# pj13_duplicate.net
KiCad netlist of a schematic drawn in EAGLE
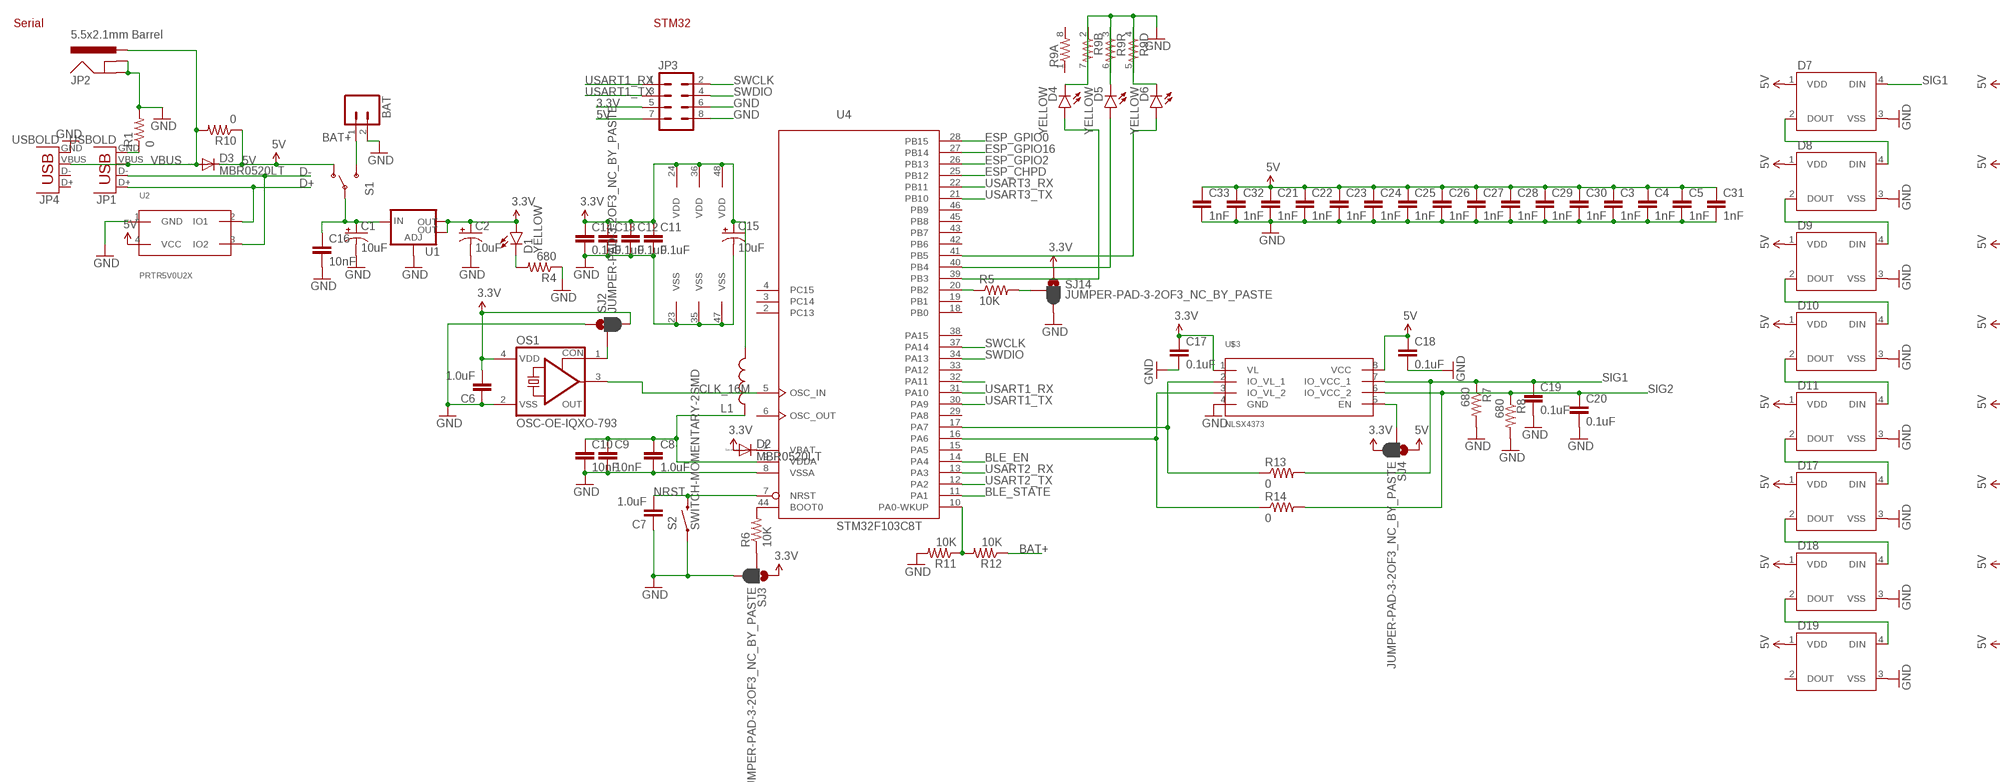
[diagram p0: schematic, sheet 1, part 1 of 2]
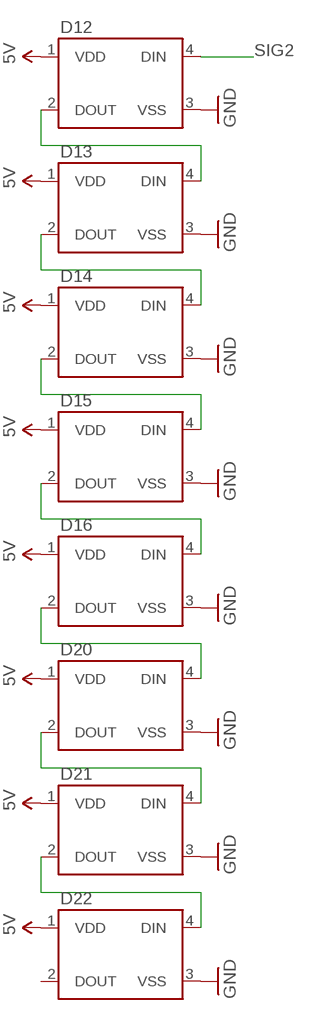
[diagram p1: schematic, sheet 1, part 2 of 2]

(export (version "E")
  (design (tool "Eeschema 10.0.6"))
  (components
    (comp (ref "BAT")
      (value "M02LOCK")
      (footprint "eagle-import:1X02_LOCK")
      (libsource (lib "eagle-import") (part "M02LOCK"))
    )
    (comp (ref "C1")
      (value "10uF")
      (footprint "eagle-import:EIA3216")
      (libsource (lib "eagle-import") (part "10UF-16V-10%(TANT)"))
    )
    (comp (ref "C2")
      (value "10uF")
      (footprint "eagle-import:EIA3216")
      (libsource (lib "eagle-import") (part "10UF-16V-10%(TANT)"))
    )
    (comp (ref "C3")
      (value "1nF")
      (footprint "eagle-import:0603-CAP")
      (libsource (lib "eagle-import") (part "0.1UF-25V-5%(0603)"))
    )
    (comp (ref "C4")
      (value "1nF")
      (footprint "eagle-import:0603-CAP")
      (libsource (lib "eagle-import") (part "0.1UF-25V-5%(0603)"))
    )
    (comp (ref "C5")
      (value "1nF")
      (footprint "eagle-import:0603-CAP")
      (libsource (lib "eagle-import") (part "0.1UF-25V-5%(0603)"))
    )
    (comp (ref "C6")
      (value "1.0uF")
      (footprint "eagle-import:0603-CAP")
      (libsource (lib "eagle-import") (part "1.0UF-16V-10%(0603)"))
    )
    (comp (ref "C7")
      (value "1.0uF")
      (footprint "eagle-import:0603-CAP")
      (libsource (lib "eagle-import") (part "1.0UF-16V-10%(0603)"))
    )
    (comp (ref "C8")
      (value "1.0uF")
      (footprint "eagle-import:0603-CAP")
      (libsource (lib "eagle-import") (part "1.0UF-16V-10%(0603)"))
    )
    (comp (ref "C9")
      (value "10nF")
      (footprint "eagle-import:0603-CAP")
      (libsource (lib "eagle-import") (part "10NF/10000PF-50V-10%(0603)"))
    )
    (comp (ref "C10")
      (value "10nF")
      (footprint "eagle-import:0603-CAP")
      (libsource (lib "eagle-import") (part "10NF/10000PF-50V-10%(0603)"))
    )
    (comp (ref "C11")
      (value "0.1uF")
      (footprint "eagle-import:0603-CAP")
      (libsource (lib "eagle-import") (part "0.1UF-25V-5%(0603)"))
    )
    (comp (ref "C12")
      (value "0.1uF")
      (footprint "eagle-import:0603-CAP")
      (libsource (lib "eagle-import") (part "0.1UF-25V-5%(0603)"))
    )
    (comp (ref "C13")
      (value "0.1uF")
      (footprint "eagle-import:0603-CAP")
      (libsource (lib "eagle-import") (part "0.1UF-25V-5%(0603)"))
    )
    (comp (ref "C14")
      (value "0.1uF")
      (footprint "eagle-import:0603-CAP")
      (libsource (lib "eagle-import") (part "0.1UF-25V-5%(0603)"))
    )
    (comp (ref "C15")
      (value "10uF")
      (footprint "eagle-import:EIA3216")
      (libsource (lib "eagle-import") (part "10UF-16V-10%(TANT)"))
    )
    (comp (ref "C16")
      (value "10nF")
      (footprint "eagle-import:0603-CAP")
      (libsource (lib "eagle-import") (part "10NF/10000PF-50V-10%(0603)"))
    )
    (comp (ref "C17")
      (value "0.1uF")
      (footprint "eagle-import:0603-CAP")
      (libsource (lib "eagle-import") (part "0.1UF-25V-5%(0603)"))
    )
    (comp (ref "C18")
      (value "0.1uF")
      (footprint "eagle-import:0603-CAP")
      (libsource (lib "eagle-import") (part "0.1UF-25V-5%(0603)"))
    )
    (comp (ref "C19")
      (value "0.1uF")
      (footprint "eagle-import:0603-CAP")
      (libsource (lib "eagle-import") (part "0.1UF-25V-5%(0603)"))
    )
    (comp (ref "C20")
      (value "0.1uF")
      (footprint "eagle-import:0603-CAP")
      (libsource (lib "eagle-import") (part "0.1UF-25V-5%(0603)"))
    )
    (comp (ref "C21")
      (value "1nF")
      (footprint "eagle-import:0603-CAP")
      (libsource (lib "eagle-import") (part "0.1UF-25V-5%(0603)"))
    )
    (comp (ref "C22")
      (value "1nF")
      (footprint "eagle-import:0603-CAP")
      (libsource (lib "eagle-import") (part "0.1UF-25V-5%(0603)"))
    )
    (comp (ref "C23")
      (value "1nF")
      (footprint "eagle-import:0603-CAP")
      (libsource (lib "eagle-import") (part "0.1UF-25V-5%(0603)"))
    )
    (comp (ref "C24")
      (value "1nF")
      (footprint "eagle-import:0603-CAP")
      (libsource (lib "eagle-import") (part "0.1UF-25V-5%(0603)"))
    )
    (comp (ref "C25")
      (value "1nF")
      (footprint "eagle-import:0603-CAP")
      (libsource (lib "eagle-import") (part "0.1UF-25V-5%(0603)"))
    )
    (comp (ref "C26")
      (value "1nF")
      (footprint "eagle-import:0603-CAP")
      (libsource (lib "eagle-import") (part "0.1UF-25V-5%(0603)"))
    )
    (comp (ref "C27")
      (value "1nF")
      (footprint "eagle-import:0603-CAP")
      (libsource (lib "eagle-import") (part "0.1UF-25V-5%(0603)"))
    )
    (comp (ref "C28")
      (value "1nF")
      (footprint "eagle-import:0603-CAP")
      (libsource (lib "eagle-import") (part "0.1UF-25V-5%(0603)"))
    )
    (comp (ref "C29")
      (value "1nF")
      (footprint "eagle-import:0603-CAP")
      (libsource (lib "eagle-import") (part "0.1UF-25V-5%(0603)"))
    )
    (comp (ref "C30")
      (value "1nF")
      (footprint "eagle-import:0603-CAP")
      (libsource (lib "eagle-import") (part "0.1UF-25V-5%(0603)"))
    )
    (comp (ref "C31")
      (value "1nF")
      (footprint "eagle-import:0603-CAP")
      (libsource (lib "eagle-import") (part "0.1UF-25V-5%(0603)"))
    )
    (comp (ref "C32")
      (value "1nF")
      (footprint "eagle-import:0603-CAP")
      (libsource (lib "eagle-import") (part "0.1UF-25V-5%(0603)"))
    )
    (comp (ref "C33")
      (value "1nF")
      (footprint "eagle-import:0603-CAP")
      (libsource (lib "eagle-import") (part "0.1UF-25V-5%(0603)"))
    )
    (comp (ref "D1")
      (value "YELLOW")
      (footprint "eagle-import:LED-1206")
      (libsource (lib "eagle-import") (part "LED-YELLOW1206"))
    )
    (comp (ref "D2")
      (value "MBR0520LT")
      (footprint "eagle-import:SOD123")
      (libsource (lib "eagle-import") (part "MBR0520LT"))
    )
    (comp (ref "D3")
      (value "MBR0520LT")
      (footprint "eagle-import:SOD123")
      (libsource (lib "eagle-import") (part "MBR0520LT"))
    )
    (comp (ref "D4")
      (value "YELLOW")
      (footprint "eagle-import:LED-1206")
      (libsource (lib "eagle-import") (part "LED-YELLOW1206"))
    )
    (comp (ref "D5")
      (value "YELLOW")
      (footprint "eagle-import:LED-1206")
      (libsource (lib "eagle-import") (part "LED-YELLOW1206"))
    )
    (comp (ref "D6")
      (value "YELLOW")
      (footprint "eagle-import:LED-1206")
      (libsource (lib "eagle-import") (part "LED-YELLOW1206"))
    )
    (comp (ref "D7")
      (value "WS2812B")
      (footprint "eagle-import:WS2812B")
      (libsource (lib "eagle-import") (part "WS2812B"))
    )
    (comp (ref "D8")
      (value "WS2812B")
      (footprint "eagle-import:WS2812B")
      (libsource (lib "eagle-import") (part "WS2812B"))
    )
    (comp (ref "D9")
      (value "WS2812B")
      (footprint "eagle-import:WS2812B")
      (libsource (lib "eagle-import") (part "WS2812B"))
    )
    (comp (ref "D10")
      (value "WS2812B")
      (footprint "eagle-import:WS2812B")
      (libsource (lib "eagle-import") (part "WS2812B"))
    )
    (comp (ref "D11")
      (value "WS2812B")
      (footprint "eagle-import:WS2812B")
      (libsource (lib "eagle-import") (part "WS2812B"))
    )
    (comp (ref "D12")
      (value "WS2812B")
      (footprint "eagle-import:WS2812B")
      (libsource (lib "eagle-import") (part "WS2812B"))
    )
    (comp (ref "D13")
      (value "WS2812B")
      (footprint "eagle-import:WS2812B")
      (libsource (lib "eagle-import") (part "WS2812B"))
    )
    (comp (ref "D14")
      (value "WS2812B")
      (footprint "eagle-import:WS2812B")
      (libsource (lib "eagle-import") (part "WS2812B"))
    )
    (comp (ref "D15")
      (value "WS2812B")
      (footprint "eagle-import:WS2812B")
      (libsource (lib "eagle-import") (part "WS2812B"))
    )
    (comp (ref "D16")
      (value "WS2812B")
      (footprint "eagle-import:WS2812B")
      (libsource (lib "eagle-import") (part "WS2812B"))
    )
    (comp (ref "D17")
      (value "WS2812B")
      (footprint "eagle-import:WS2812B")
      (libsource (lib "eagle-import") (part "WS2812B"))
    )
    (comp (ref "D18")
      (value "WS2812B")
      (footprint "eagle-import:WS2812B")
      (libsource (lib "eagle-import") (part "WS2812B"))
    )
    (comp (ref "D19")
      (value "WS2812B")
      (footprint "eagle-import:WS2812B")
      (libsource (lib "eagle-import") (part "WS2812B"))
    )
    (comp (ref "D20")
      (value "WS2812B")
      (footprint "eagle-import:WS2812B")
      (libsource (lib "eagle-import") (part "WS2812B"))
    )
    (comp (ref "D21")
      (value "WS2812B")
      (footprint "eagle-import:WS2812B")
      (libsource (lib "eagle-import") (part "WS2812B"))
    )
    (comp (ref "D22")
      (value "WS2812B")
      (footprint "eagle-import:WS2812B")
      (libsource (lib "eagle-import") (part "WS2812B"))
    )
    (comp (ref "JP1")
      (value "USBOLD")
      (footprint "eagle-import:USB-MINIB-OLD")
      (libsource (lib "eagle-import") (part "USBOLD"))
    )
    (comp (ref "JP2")
      (value "5.5x2.1mm Barrel")
      (footprint "eagle-import:POWER_JACK_SMD")
      (libsource (lib "eagle-import") (part "POWER_JACKSMD"))
    )
    (comp (ref "JP3")
      (value "M04X2SMD")
      (footprint "eagle-import:2X4_SMD")
      (libsource (lib "eagle-import") (part "M04X2SMD"))
    )
    (comp (ref "JP4")
      (value "USBOLD")
      (footprint "eagle-import:USB-MINIB-OLD")
      (libsource (lib "eagle-import") (part "USBOLD"))
    )
    (comp (ref "L1")
      (value "INDUCTOR0603")
      (footprint "eagle-import:0603")
      (libsource (lib "eagle-import") (part "INDUCTOR0603"))
    )
    (comp (ref "OS1")
      (value "OSC-OE-IQXO-793")
      (footprint "eagle-import:2.5X2-4-PAD")
      (libsource (lib "eagle-import") (part "OSC-OE-IQXO-793"))
    )
    (comp (ref "R1")
      (value "0")
      (footprint "eagle-import:0603")
      (libsource (lib "eagle-import") (part "0OHM-1/10W-5%(0603)"))
    )
    (comp (ref "R4")
      (value "680")
      (footprint "eagle-import:0603-RES")
      (libsource (lib "eagle-import") (part "680OHM1/10W5%(0603)"))
    )
    (comp (ref "R5")
      (value "10K")
      (footprint "eagle-import:0603-RES")
      (libsource (lib "eagle-import") (part "10KOHM-1/10W-1%(0603)0603"))
    )
    (comp (ref "R6")
      (value "10K")
      (footprint "eagle-import:0603-RES")
      (libsource (lib "eagle-import") (part "10KOHM-1/10W-1%(0603)0603"))
    )
    (comp (ref "R7")
      (value "680")
      (footprint "eagle-import:0603-RES")
      (libsource (lib "eagle-import") (part "680OHM1/10W5%(0603)"))
    )
    (comp (ref "R8")
      (value "680")
      (footprint "eagle-import:0603-RES")
      (libsource (lib "eagle-import") (part "680OHM1/10W5%(0603)"))
    )
    (comp (ref "R9")
      (value "RESISTOR-ARRAY0603-ARV")
      (footprint "eagle-import:0603-ARV")
      (libsource (lib "eagle-import") (part "RESISTOR-ARRAY0603-ARV"))
    )
    (comp (ref "R10")
      (value "0")
      (footprint "eagle-import:0603")
      (libsource (lib "eagle-import") (part "0OHM-1/10W-5%(0603)"))
    )
    (comp (ref "R11")
      (value "10K")
      (footprint "eagle-import:0603-RES")
      (libsource (lib "eagle-import") (part "10KOHM-1/10W-1%(0603)0603"))
    )
    (comp (ref "R12")
      (value "10K")
      (footprint "eagle-import:0603-RES")
      (libsource (lib "eagle-import") (part "10KOHM-1/10W-1%(0603)0603"))
    )
    (comp (ref "R13")
      (value "0")
      (footprint "eagle-import:0603-RES")
      (libsource (lib "eagle-import") (part "680OHM1/10W5%(0603)"))
    )
    (comp (ref "R14")
      (value "0")
      (footprint "eagle-import:0603-RES")
      (libsource (lib "eagle-import") (part "680OHM1/10W5%(0603)"))
    )
    (comp (ref "S1")
      (value "SWITCH-SPDTSMD")
      (footprint "eagle-import:AYZ0202")
      (libsource (lib "eagle-import") (part "SWITCH-SPDTSMD"))
    )
    (comp (ref "S2")
      (value "SWITCH-MOMENTARY-2SMD")
      (footprint "eagle-import:TACTILE-SWITCH-SMD")
      (libsource (lib "eagle-import") (part "SWITCH-MOMENTARY-2SMD"))
    )
    (comp (ref "SJ2")
      (value "JUMPER-PAD-3-2OF3_NC_BY_PASTE")
      (footprint "eagle-import:PAD-JUMPER-3-2OF3_NC_BY_PASTE_YES_SILK_FULL_BOX")
      (libsource (lib "eagle-import") (part "JUMPER-PAD-3-2OF3_NC_BY_PASTE"))
    )
    (comp (ref "SJ3")
      (value "JUMPER-PAD-3-2OF3_NC_BY_PASTE")
      (footprint "eagle-import:PAD-JUMPER-3-2OF3_NC_BY_PASTE_YES_SILK_FULL_BOX")
      (libsource (lib "eagle-import") (part "JUMPER-PAD-3-2OF3_NC_BY_PASTE"))
    )
    (comp (ref "SJ4")
      (value "JUMPER-PAD-3-2OF3_NC_BY_PASTE")
      (footprint "eagle-import:PAD-JUMPER-3-2OF3_NC_BY_PASTE_YES_SILK_FULL_BOX")
      (libsource (lib "eagle-import") (part "JUMPER-PAD-3-2OF3_NC_BY_PASTE"))
    )
    (comp (ref "SJ14")
      (value "JUMPER-PAD-3-2OF3_NC_BY_PASTE")
      (footprint "eagle-import:PAD-JUMPER-3-2OF3_NC_BY_PASTE_YES_SILK_FULL_BOX")
      (libsource (lib "eagle-import") (part "JUMPER-PAD-3-2OF3_NC_BY_PASTE"))
    )
    (comp (ref "U$3")
      (value "NLSX4373")
      (footprint "eagle-import:SO08")
      (libsource (lib "eagle-import") (part "NLSX4373"))
    )
    (comp (ref "U1")
      (value "V_REG_LM1117SOT223")
      (footprint "eagle-import:SOT223")
      (libsource (lib "eagle-import") (part "V_REG_LM1117SOT223"))
    )
    (comp (ref "U2")
      (value "PRTR5V0U2X")
      (footprint "eagle-import:SOT143")
      (libsource (lib "eagle-import") (part "PRTR5V0U2X"))
    )
    (comp (ref "U4")
      (value "STM32F103C8T")
      (footprint "eagle-import:LQFP48")
      (libsource (lib "eagle-import") (part "STM32F103CT8"))
    )
  )
  (nets
    (net (code "1") (name "/BAT+") (class "Default")
      (node (ref "BAT") (pin "1") (pinfunction "1_1") (pintype "passive"))
      (node (ref "R12") (pin "1") (pinfunction "1_1") (pintype "passive"))
      (node (ref "S1") (pin "3") (pinfunction "S_3") (pintype "passive"))
    )
    (net (code "2") (name "/BLE_EN") (class "Default")
      (node (ref "U4") (pin "14") (pinfunction "PA4_14") (pintype "bidirectional"))
    )
    (net (code "3") (name "/BLE_STATE") (class "Default")
      (node (ref "U4") (pin "11") (pinfunction "PA1_11") (pintype "bidirectional"))
    )
    (net (code "4") (name "/CLK_16M") (class "Default")
      (node (ref "OS1") (pin "3") (pinfunction "OUT_3") (pintype "output"))
      (node (ref "U4") (pin "5") (pinfunction "OSC_IN_5") (pintype "bidirectional"))
    )
    (net (code "5") (name "/D+") (class "Default")
      (node (ref "JP1") (pin "D+") (pinfunction "D+_D+") (pintype "bidirectional"))
      (node (ref "U2") (pin "2") (pinfunction "IO1_2") (pintype "bidirectional"))
    )
    (net (code "6") (name "/D-") (class "Default")
      (node (ref "JP1") (pin "D-") (pinfunction "D-_D-") (pintype "bidirectional"))
      (node (ref "U2") (pin "3") (pinfunction "IO2_3") (pintype "bidirectional"))
    )
    (net (code "7") (name "/ESP_CHPD") (class "Default")
      (node (ref "U4") (pin "25") (pinfunction "PB12_25") (pintype "bidirectional"))
    )
    (net (code "8") (name "/ESP_GPIO0") (class "Default")
      (node (ref "U4") (pin "28") (pinfunction "PB15_28") (pintype "bidirectional"))
    )
    (net (code "9") (name "/ESP_GPIO2") (class "Default")
      (node (ref "U4") (pin "26") (pinfunction "PB13_26") (pintype "bidirectional"))
    )
    (net (code "10") (name "/ESP_GPIO16") (class "Default")
      (node (ref "U4") (pin "27") (pinfunction "PB14_27") (pintype "bidirectional"))
    )
    (net (code "11") (name "/NRST") (class "Default")
      (node (ref "C7") (pin "2") (pinfunction "2_2") (pintype "passive"))
      (node (ref "S2") (pin "3") (pinfunction "2_3") (pintype "passive"))
      (node (ref "U4") (pin "7") (pinfunction "NRST_7") (pintype "bidirectional"))
    )
    (net (code "12") (name "/SIG1") (class "Default")
      (node (ref "C19") (pin "1") (pinfunction "1_1") (pintype "passive"))
      (node (ref "D7") (pin "4") (pinfunction "DIN_4") (pintype "input"))
      (node (ref "R13") (pin "2") (pinfunction "2_2") (pintype "passive"))
      (node (ref "R7") (pin "1") (pinfunction "1_1") (pintype "passive"))
      (node (ref "U$3") (pin "7") (pinfunction "IO_VCC_1_7") (pintype "bidirectional"))
    )
    (net (code "13") (name "/SIG2") (class "Default")
      (node (ref "C20") (pin "1") (pinfunction "1_1") (pintype "passive"))
      (node (ref "D12") (pin "4") (pinfunction "DIN_4") (pintype "input"))
      (node (ref "R14") (pin "2") (pinfunction "2_2") (pintype "passive"))
      (node (ref "R8") (pin "1") (pinfunction "1_1") (pintype "passive"))
      (node (ref "U$3") (pin "6") (pinfunction "IO_VCC_2_6") (pintype "bidirectional"))
    )
    (net (code "14") (name "/SWCLK") (class "Default")
      (node (ref "JP3") (pin "2") (pinfunction "2_2") (pintype "passive"))
      (node (ref "U4") (pin "37") (pinfunction "PA14_37") (pintype "bidirectional"))
    )
    (net (code "15") (name "/SWDIO") (class "Default")
      (node (ref "JP3") (pin "4") (pinfunction "4_4") (pintype "passive"))
      (node (ref "U4") (pin "34") (pinfunction "PA13_34") (pintype "bidirectional"))
    )
    (net (code "16") (name "/USART1_RX") (class "Default")
      (node (ref "JP3") (pin "1") (pinfunction "1_1") (pintype "passive"))
      (node (ref "U4") (pin "31") (pinfunction "PA10_31") (pintype "bidirectional"))
    )
    (net (code "17") (name "/USART1_TX") (class "Default")
      (node (ref "JP3") (pin "3") (pinfunction "3_3") (pintype "passive"))
      (node (ref "U4") (pin "30") (pinfunction "PA9_30") (pintype "bidirectional"))
    )
    (net (code "18") (name "/USART2_RX") (class "Default")
      (node (ref "U4") (pin "13") (pinfunction "PA3_13") (pintype "bidirectional"))
    )
    (net (code "19") (name "/USART2_TX") (class "Default")
      (node (ref "U4") (pin "12") (pinfunction "PA2_12") (pintype "bidirectional"))
    )
    (net (code "20") (name "/USART3_RX") (class "Default")
      (node (ref "U4") (pin "22") (pinfunction "PB11_22") (pintype "bidirectional"))
    )
    (net (code "21") (name "/USART3_TX") (class "Default")
      (node (ref "U4") (pin "21") (pinfunction "PB10_21") (pintype "bidirectional"))
    )
    (net (code "22") (name "/VBUS") (class "Default")
      (node (ref "D3") (pin "A") (pinfunction "A_A") (pintype "passive"))
      (node (ref "JP1") (pin "VBUS") (pinfunction "VBUS_VBUS") (pintype "bidirectional"))
      (node (ref "JP2") (pin "VIN0") (pinfunction "PWR_VIN0") (pintype "bidirectional"))
      (node (ref "JP4") (pin "VBUS") (pinfunction "VBUS_VBUS") (pintype "bidirectional"))
      (node (ref "R10") (pin "2") (pinfunction "2_2") (pintype "passive"))
    )
    (net (code "23") (name "3.3V") (class "Default")
      (node (ref "C11") (pin "1") (pinfunction "1_1") (pintype "passive"))
      (node (ref "C12") (pin "1") (pinfunction "1_1") (pintype "passive"))
      (node (ref "C13") (pin "1") (pinfunction "1_1") (pintype "passive"))
      (node (ref "C14") (pin "1") (pinfunction "1_1") (pintype "passive"))
      (node (ref "C15") (pin "A") (pinfunction "+_A") (pintype "passive"))
      (node (ref "C17") (pin "1") (pinfunction "1_1") (pintype "passive"))
      (node (ref "C2") (pin "A") (pinfunction "+_A") (pintype "passive"))
      (node (ref "C6") (pin "2") (pinfunction "2_2") (pintype "passive"))
      (node (ref "D1") (pin "A") (pinfunction "A_A") (pintype "passive"))
      (node (ref "D2") (pin "A") (pinfunction "A_A") (pintype "passive"))
      (node (ref "JP3") (pin "5") (pinfunction "5_5") (pintype "passive"))
      (node (ref "L1") (pin "2") (pinfunction "2_2") (pintype "passive"))
      (node (ref "OS1") (pin "4") (pinfunction "VDD_4") (pintype "power_in"))
      (node (ref "SJ14") (pin "1") (pinfunction "1_1") (pintype "passive"))
      (node (ref "SJ2") (pin "3") (pinfunction "3_3") (pintype "passive"))
      (node (ref "SJ3") (pin "1") (pinfunction "1_1") (pintype "passive"))
      (node (ref "SJ4") (pin "3") (pinfunction "3_3") (pintype "passive"))
      (node (ref "U$3") (pin "1") (pinfunction "VL_1") (pintype "bidirectional"))
      (node (ref "U1") (pin "2") (pinfunction "OUT_2") (pintype "output"))
      (node (ref "U1") (pin "4") (pinfunction "OUT_4") (pintype "output"))
      (node (ref "U4") (pin "24") (pinfunction "VDD_24") (pintype "power_in"))
      (node (ref "U4") (pin "36") (pinfunction "VDD_36") (pintype "power_in"))
      (node (ref "U4") (pin "48") (pinfunction "VDD_48") (pintype "power_in"))
    )
    (net (code "24") (name "5V") (class "Default")
      (node (ref "C18") (pin "1") (pinfunction "1_1") (pintype "passive"))
      (node (ref "C21") (pin "1") (pinfunction "1_1") (pintype "passive"))
      (node (ref "C22") (pin "1") (pinfunction "1_1") (pintype "passive"))
      (node (ref "C23") (pin "1") (pinfunction "1_1") (pintype "passive"))
      (node (ref "C24") (pin "1") (pinfunction "1_1") (pintype "passive"))
      (node (ref "C25") (pin "1") (pinfunction "1_1") (pintype "passive"))
      (node (ref "C26") (pin "1") (pinfunction "1_1") (pintype "passive"))
      (node (ref "C27") (pin "1") (pinfunction "1_1") (pintype "passive"))
      (node (ref "C28") (pin "1") (pinfunction "1_1") (pintype "passive"))
      (node (ref "C29") (pin "1") (pinfunction "1_1") (pintype "passive"))
      (node (ref "C3") (pin "1") (pinfunction "1_1") (pintype "passive"))
      (node (ref "C30") (pin "1") (pinfunction "1_1") (pintype "passive"))
      (node (ref "C31") (pin "1") (pinfunction "1_1") (pintype "passive"))
      (node (ref "C32") (pin "1") (pinfunction "1_1") (pintype "passive"))
      (node (ref "C33") (pin "1") (pinfunction "1_1") (pintype "passive"))
      (node (ref "C4") (pin "1") (pinfunction "1_1") (pintype "passive"))
      (node (ref "C5") (pin "1") (pinfunction "1_1") (pintype "passive"))
      (node (ref "D10") (pin "1") (pinfunction "VDD_1") (pintype "power_in"))
      (node (ref "D11") (pin "1") (pinfunction "VDD_1") (pintype "power_in"))
      (node (ref "D12") (pin "1") (pinfunction "VDD_1") (pintype "power_in"))
      (node (ref "D13") (pin "1") (pinfunction "VDD_1") (pintype "power_in"))
      (node (ref "D14") (pin "1") (pinfunction "VDD_1") (pintype "power_in"))
      (node (ref "D15") (pin "1") (pinfunction "VDD_1") (pintype "power_in"))
      (node (ref "D16") (pin "1") (pinfunction "VDD_1") (pintype "power_in"))
      (node (ref "D17") (pin "1") (pinfunction "VDD_1") (pintype "power_in"))
      (node (ref "D18") (pin "1") (pinfunction "VDD_1") (pintype "power_in"))
      (node (ref "D19") (pin "1") (pinfunction "VDD_1") (pintype "power_in"))
      (node (ref "D20") (pin "1") (pinfunction "VDD_1") (pintype "power_in"))
      (node (ref "D21") (pin "1") (pinfunction "VDD_1") (pintype "power_in"))
      (node (ref "D22") (pin "1") (pinfunction "VDD_1") (pintype "power_in"))
      (node (ref "D3") (pin "C") (pinfunction "C_C") (pintype "passive"))
      (node (ref "D7") (pin "1") (pinfunction "VDD_1") (pintype "power_in"))
      (node (ref "D8") (pin "1") (pinfunction "VDD_1") (pintype "power_in"))
      (node (ref "D9") (pin "1") (pinfunction "VDD_1") (pintype "power_in"))
      (node (ref "JP3") (pin "7") (pinfunction "7_7") (pintype "passive"))
      (node (ref "R10") (pin "1") (pinfunction "1_1") (pintype "passive"))
      (node (ref "S1") (pin "1") (pinfunction "O_1") (pintype "passive"))
      (node (ref "SJ4") (pin "1") (pinfunction "1_1") (pintype "passive"))
      (node (ref "U$3") (pin "8") (pinfunction "VCC_8") (pintype "bidirectional"))
      (node (ref "U2") (pin "4") (pinfunction "VCC_4") (pintype "bidirectional"))
    )
    (net (code "25") (name "GND") (class "Default")
      (node (ref "BAT") (pin "2") (pinfunction "2_2") (pintype "passive"))
      (node (ref "C1") (pin "C") (pinfunction "-_C") (pintype "passive"))
      (node (ref "C10") (pin "2") (pinfunction "2_2") (pintype "passive"))
      (node (ref "C11") (pin "2") (pinfunction "2_2") (pintype "passive"))
      (node (ref "C12") (pin "2") (pinfunction "2_2") (pintype "passive"))
      (node (ref "C13") (pin "2") (pinfunction "2_2") (pintype "passive"))
      (node (ref "C14") (pin "2") (pinfunction "2_2") (pintype "passive"))
      (node (ref "C15") (pin "C") (pinfunction "-_C") (pintype "passive"))
      (node (ref "C16") (pin "2") (pinfunction "2_2") (pintype "passive"))
      (node (ref "C17") (pin "2") (pinfunction "2_2") (pintype "passive"))
      (node (ref "C18") (pin "2") (pinfunction "2_2") (pintype "passive"))
      (node (ref "C19") (pin "2") (pinfunction "2_2") (pintype "passive"))
      (node (ref "C2") (pin "C") (pinfunction "-_C") (pintype "passive"))
      (node (ref "C20") (pin "2") (pinfunction "2_2") (pintype "passive"))
      (node (ref "C21") (pin "2") (pinfunction "2_2") (pintype "passive"))
      (node (ref "C22") (pin "2") (pinfunction "2_2") (pintype "passive"))
      (node (ref "C23") (pin "2") (pinfunction "2_2") (pintype "passive"))
      (node (ref "C24") (pin "2") (pinfunction "2_2") (pintype "passive"))
      (node (ref "C25") (pin "2") (pinfunction "2_2") (pintype "passive"))
      (node (ref "C26") (pin "2") (pinfunction "2_2") (pintype "passive"))
      (node (ref "C27") (pin "2") (pinfunction "2_2") (pintype "passive"))
      (node (ref "C28") (pin "2") (pinfunction "2_2") (pintype "passive"))
      (node (ref "C29") (pin "2") (pinfunction "2_2") (pintype "passive"))
      (node (ref "C3") (pin "2") (pinfunction "2_2") (pintype "passive"))
      (node (ref "C30") (pin "2") (pinfunction "2_2") (pintype "passive"))
      (node (ref "C31") (pin "2") (pinfunction "2_2") (pintype "passive"))
      (node (ref "C32") (pin "2") (pinfunction "2_2") (pintype "passive"))
      (node (ref "C33") (pin "2") (pinfunction "2_2") (pintype "passive"))
      (node (ref "C4") (pin "2") (pinfunction "2_2") (pintype "passive"))
      (node (ref "C5") (pin "2") (pinfunction "2_2") (pintype "passive"))
      (node (ref "C6") (pin "1") (pinfunction "1_1") (pintype "passive"))
      (node (ref "C7") (pin "1") (pinfunction "1_1") (pintype "passive"))
      (node (ref "C8") (pin "2") (pinfunction "2_2") (pintype "passive"))
      (node (ref "C9") (pin "2") (pinfunction "2_2") (pintype "passive"))
      (node (ref "D10") (pin "3") (pinfunction "VSS_3") (pintype "power_in"))
      (node (ref "D11") (pin "3") (pinfunction "VSS_3") (pintype "power_in"))
      (node (ref "D12") (pin "3") (pinfunction "VSS_3") (pintype "power_in"))
      (node (ref "D13") (pin "3") (pinfunction "VSS_3") (pintype "power_in"))
      (node (ref "D14") (pin "3") (pinfunction "VSS_3") (pintype "power_in"))
      (node (ref "D15") (pin "3") (pinfunction "VSS_3") (pintype "power_in"))
      (node (ref "D16") (pin "3") (pinfunction "VSS_3") (pintype "power_in"))
      (node (ref "D17") (pin "3") (pinfunction "VSS_3") (pintype "power_in"))
      (node (ref "D18") (pin "3") (pinfunction "VSS_3") (pintype "power_in"))
      (node (ref "D19") (pin "3") (pinfunction "VSS_3") (pintype "power_in"))
      (node (ref "D20") (pin "3") (pinfunction "VSS_3") (pintype "power_in"))
      (node (ref "D21") (pin "3") (pinfunction "VSS_3") (pintype "power_in"))
      (node (ref "D22") (pin "3") (pinfunction "VSS_3") (pintype "power_in"))
      (node (ref "D7") (pin "3") (pinfunction "VSS_3") (pintype "power_in"))
      (node (ref "D8") (pin "3") (pinfunction "VSS_3") (pintype "power_in"))
      (node (ref "D9") (pin "3") (pinfunction "VSS_3") (pintype "power_in"))
      (node (ref "JP2") (pin "GND") (pinfunction "GNDBREAK_GND") (pintype "bidirectional"))
      (node (ref "JP2") (pin "P$4") (pinfunction "GND_P$4") (pintype "bidirectional"))
      (node (ref "JP3") (pin "6") (pinfunction "6_6") (pintype "passive"))
      (node (ref "JP3") (pin "8") (pinfunction "8_8") (pintype "passive"))
      (node (ref "JP4") (pin "GND") (pinfunction "GND_GND") (pintype "bidirectional"))
      (node (ref "OS1") (pin "2") (pinfunction "VSS_2") (pintype "power_in"))
      (node (ref "R1") (pin "2") (pinfunction "2_2") (pintype "passive"))
      (node (ref "R11") (pin "2") (pinfunction "2_2") (pintype "passive"))
      (node (ref "R4") (pin "1") (pinfunction "1_1") (pintype "passive"))
      (node (ref "R7") (pin "2") (pinfunction "2_2") (pintype "passive"))
      (node (ref "R8") (pin "2") (pinfunction "2_2") (pintype "passive"))
      (node (ref "R9") (pin "5") (pinfunction "2_5") (pintype "passive"))
      (node (ref "R9") (pin "6") (pinfunction "2_6") (pintype "passive"))
      (node (ref "R9") (pin "7") (pinfunction "2_7") (pintype "passive"))
      (node (ref "S2") (pin "1") (pinfunction "1_1") (pintype "passive"))
      (node (ref "SJ14") (pin "3") (pinfunction "3_3") (pintype "passive"))
      (node (ref "SJ2") (pin "1") (pinfunction "1_1") (pintype "passive"))
      (node (ref "SJ3") (pin "3") (pinfunction "3_3") (pintype "passive"))
      (node (ref "U$3") (pin "4") (pinfunction "GND_4") (pintype "bidirectional"))
      (node (ref "U1") (pin "1") (pinfunction "ADJ_1") (pintype "input"))
      (node (ref "U2") (pin "1") (pinfunction "GND_1") (pintype "bidirectional"))
      (node (ref "U4") (pin "23") (pinfunction "VSS_23") (pintype "power_in"))
      (node (ref "U4") (pin "35") (pinfunction "VSS_35") (pintype "power_in"))
      (node (ref "U4") (pin "47") (pinfunction "VSS_47") (pintype "power_in"))
      (node (ref "U4") (pin "8") (pinfunction "VSSA_8") (pintype "power_in"))
    )
    (net (code "26") (name "Net-(C1-+)") (class "Default")
      (node (ref "C1") (pin "A") (pinfunction "+_A") (pintype "passive"))
      (node (ref "C16") (pin "1") (pinfunction "1_1") (pintype "passive"))
      (node (ref "S1") (pin "2") (pinfunction "P_2") (pintype "passive"))
      (node (ref "U1") (pin "3") (pinfunction "IN_3") (pintype "input"))
    )
    (net (code "27") (name "Net-(D1-PadC)") (class "Default")
      (node (ref "D1") (pin "C") (pinfunction "C_C") (pintype "passive"))
      (node (ref "R4") (pin "2") (pinfunction "2_2") (pintype "passive"))
    )
    (net (code "28") (name "Net-(D7-DOUT)") (class "Default")
      (node (ref "D7") (pin "2") (pinfunction "DOUT_2") (pintype "output"))
      (node (ref "D8") (pin "4") (pinfunction "DIN_4") (pintype "input"))
    )
    (net (code "29") (name "Net-(D8-DOUT)") (class "Default")
      (node (ref "D8") (pin "2") (pinfunction "DOUT_2") (pintype "output"))
      (node (ref "D9") (pin "4") (pinfunction "DIN_4") (pintype "input"))
    )
    (net (code "30") (name "Net-(D10-DIN)") (class "Default")
      (node (ref "D10") (pin "4") (pinfunction "DIN_4") (pintype "input"))
      (node (ref "D9") (pin "2") (pinfunction "DOUT_2") (pintype "output"))
    )
    (net (code "31") (name "Net-(D10-DOUT)") (class "Default")
      (node (ref "D10") (pin "2") (pinfunction "DOUT_2") (pintype "output"))
      (node (ref "D11") (pin "4") (pinfunction "DIN_4") (pintype "input"))
    )
    (net (code "32") (name "Net-(D11-DOUT)") (class "Default")
      (node (ref "D11") (pin "2") (pinfunction "DOUT_2") (pintype "output"))
      (node (ref "D17") (pin "4") (pinfunction "DIN_4") (pintype "input"))
    )
    (net (code "33") (name "Net-(D12-DOUT)") (class "Default")
      (node (ref "D12") (pin "2") (pinfunction "DOUT_2") (pintype "output"))
      (node (ref "D13") (pin "4") (pinfunction "DIN_4") (pintype "input"))
    )
    (net (code "34") (name "Net-(D13-DOUT)") (class "Default")
      (node (ref "D13") (pin "2") (pinfunction "DOUT_2") (pintype "output"))
      (node (ref "D14") (pin "4") (pinfunction "DIN_4") (pintype "input"))
    )
    (net (code "35") (name "Net-(D14-DOUT)") (class "Default")
      (node (ref "D14") (pin "2") (pinfunction "DOUT_2") (pintype "output"))
      (node (ref "D15") (pin "4") (pinfunction "DIN_4") (pintype "input"))
    )
    (net (code "36") (name "Net-(D15-DOUT)") (class "Default")
      (node (ref "D15") (pin "2") (pinfunction "DOUT_2") (pintype "output"))
      (node (ref "D16") (pin "4") (pinfunction "DIN_4") (pintype "input"))
    )
    (net (code "37") (name "Net-(D16-DOUT)") (class "Default")
      (node (ref "D16") (pin "2") (pinfunction "DOUT_2") (pintype "output"))
      (node (ref "D20") (pin "4") (pinfunction "DIN_4") (pintype "input"))
    )
    (net (code "38") (name "Net-(D17-DOUT)") (class "Default")
      (node (ref "D17") (pin "2") (pinfunction "DOUT_2") (pintype "output"))
      (node (ref "D18") (pin "4") (pinfunction "DIN_4") (pintype "input"))
    )
    (net (code "39") (name "Net-(D18-DOUT)") (class "Default")
      (node (ref "D18") (pin "2") (pinfunction "DOUT_2") (pintype "output"))
      (node (ref "D19") (pin "4") (pinfunction "DIN_4") (pintype "input"))
    )
    (net (code "40") (name "Net-(D20-DOUT)") (class "Default")
      (node (ref "D20") (pin "2") (pinfunction "DOUT_2") (pintype "output"))
      (node (ref "D21") (pin "4") (pinfunction "DIN_4") (pintype "input"))
    )
    (net (code "41") (name "Net-(D21-DOUT)") (class "Default")
      (node (ref "D21") (pin "2") (pinfunction "DOUT_2") (pintype "output"))
      (node (ref "D22") (pin "4") (pinfunction "DIN_4") (pintype "input"))
    )
    (net (code "42") (name "Net-(JP1-PadGND)") (class "Default")
      (node (ref "JP1") (pin "GND") (pinfunction "GND_GND") (pintype "bidirectional"))
      (node (ref "R1") (pin "1") (pinfunction "1_1") (pintype "passive"))
    )
    (net (code "43") (name "Net-(OS1-CON)") (class "Default")
      (node (ref "OS1") (pin "1") (pinfunction "CON_1") (pintype "input"))
      (node (ref "SJ2") (pin "2") (pinfunction "2_2") (pintype "passive"))
    )
    (net (code "44") (name "Net-(R5-Pad2)") (class "Default")
      (node (ref "R5") (pin "2") (pinfunction "2_2") (pintype "passive"))
      (node (ref "SJ14") (pin "2") (pinfunction "2_2") (pintype "passive"))
    )
    (net (code "45") (name "Net-(R6-Pad1)") (class "Default")
      (node (ref "R6") (pin "1") (pinfunction "1_1") (pintype "passive"))
      (node (ref "SJ3") (pin "2") (pinfunction "2_2") (pintype "passive"))
    )
    (net (code "46") (name "Net-(R9B-1)") (class "Default")
      (node (ref "D4") (pin "C") (pinfunction "C_C") (pintype "passive"))
      (node (ref "R9") (pin "2") (pinfunction "1_2") (pintype "passive"))
    )
    (net (code "47") (name "Net-(R9C-1)") (class "Default")
      (node (ref "D6") (pin "C") (pinfunction "C_C") (pintype "passive"))
      (node (ref "R9") (pin "4") (pinfunction "1_4") (pintype "passive"))
    )
    (net (code "48") (name "Net-(R9D-1)") (class "Default")
      (node (ref "D5") (pin "C") (pinfunction "C_C") (pintype "passive"))
      (node (ref "R9") (pin "3") (pinfunction "1_3") (pintype "passive"))
    )
    (net (code "49") (name "Net-(U$3-EN)") (class "Default")
      (node (ref "SJ4") (pin "2") (pinfunction "2_2") (pintype "passive"))
      (node (ref "U$3") (pin "5") (pinfunction "EN_5") (pintype "bidirectional"))
    )
    (net (code "50") (name "Net-(U$3-IO_VL_1)") (class "Default")
      (node (ref "R13") (pin "1") (pinfunction "1_1") (pintype "passive"))
      (node (ref "U$3") (pin "2") (pinfunction "IO_VL_1_2") (pintype "bidirectional"))
      (node (ref "U4") (pin "17") (pinfunction "PA7_17") (pintype "bidirectional"))
    )
    (net (code "51") (name "Net-(U$3-IO_VL_2)") (class "Default")
      (node (ref "R14") (pin "1") (pinfunction "1_1") (pintype "passive"))
      (node (ref "U$3") (pin "3") (pinfunction "IO_VL_2_3") (pintype "bidirectional"))
      (node (ref "U4") (pin "16") (pinfunction "PA6_16") (pintype "bidirectional"))
    )
    (net (code "52") (name "Net-(U4A-BOOT0)") (class "Default")
      (node (ref "R6") (pin "2") (pinfunction "2_2") (pintype "passive"))
      (node (ref "U4") (pin "44") (pinfunction "BOOT0_44") (pintype "input"))
    )
    (net (code "53") (name "Net-(U4A-PA0-WKUP)") (class "Default")
      (node (ref "R11") (pin "1") (pinfunction "1_1") (pintype "passive"))
      (node (ref "R12") (pin "2") (pinfunction "2_2") (pintype "passive"))
      (node (ref "U4") (pin "10") (pinfunction "PA0-WKUP_10") (pintype "bidirectional"))
    )
    (net (code "54") (name "Net-(U4A-PB2)") (class "Default")
      (node (ref "R5") (pin "1") (pinfunction "1_1") (pintype "passive"))
      (node (ref "U4") (pin "20") (pinfunction "PB2_20") (pintype "bidirectional"))
    )
    (net (code "55") (name "Net-(U4A-PB3)") (class "Default")
      (node (ref "D4") (pin "A") (pinfunction "A_A") (pintype "passive"))
      (node (ref "U4") (pin "39") (pinfunction "PB3_39") (pintype "bidirectional"))
    )
    (net (code "56") (name "Net-(U4A-PB4)") (class "Default")
      (node (ref "D5") (pin "A") (pinfunction "A_A") (pintype "passive"))
      (node (ref "U4") (pin "40") (pinfunction "PB4_40") (pintype "bidirectional"))
    )
    (net (code "57") (name "Net-(U4A-PB5)") (class "Default")
      (node (ref "D6") (pin "A") (pinfunction "A_A") (pintype "passive"))
      (node (ref "U4") (pin "41") (pinfunction "PB5_41") (pintype "bidirectional"))
    )
    (net (code "58") (name "Net-(U4A-VBAT)") (class "Default")
      (node (ref "D2") (pin "C") (pinfunction "C_C") (pintype "passive"))
      (node (ref "U4") (pin "1") (pinfunction "VBAT_1") (pintype "power_in"))
    )
    (net (code "59") (name "Net-(U4A-VDDA)") (class "Default")
      (node (ref "C10") (pin "1") (pinfunction "1_1") (pintype "passive"))
      (node (ref "C8") (pin "1") (pinfunction "1_1") (pintype "passive"))
      (node (ref "C9") (pin "1") (pinfunction "1_1") (pintype "passive"))
      (node (ref "L1") (pin "1") (pinfunction "1_1") (pintype "passive"))
      (node (ref "U4") (pin "9") (pinfunction "VDDA_9") (pintype "power_in"))
    )
    (net (code "60") (name "unconnected-(D19-DOUT-Pad2)") (class "Default")
      (node (ref "D19") (pin "2") (pinfunction "DOUT_2") (pintype "output"))
    )
    (net (code "61") (name "unconnected-(D22-DOUT-Pad2)") (class "Default")
      (node (ref "D22") (pin "2") (pinfunction "DOUT_2") (pintype "output"))
    )
    (net (code "62") (name "unconnected-(JP4-PadD+)") (class "Default")
      (node (ref "JP4") (pin "D+") (pinfunction "D+_D+") (pintype "bidirectional"))
    )
    (net (code "63") (name "unconnected-(JP4-PadD-)") (class "Default")
      (node (ref "JP4") (pin "D-") (pinfunction "D-_D-") (pintype "bidirectional"))
    )
    (net (code "64") (name "unconnected-(R9-Pad1)") (class "Default")
      (node (ref "R9") (pin "1") (pinfunction "1_1") (pintype "passive"))
    )
    (net (code "65") (name "unconnected-(R9A-2-Pad8)") (class "Default")
      (node (ref "R9") (pin "8") (pinfunction "2_8") (pintype "passive"))
    )
    (net (code "66") (name "unconnected-(U4A-OSC_OUT-Pad6)") (class "Default")
      (node (ref "U4") (pin "6") (pinfunction "OSC_OUT_6") (pintype "bidirectional"))
    )
    (net (code "67") (name "unconnected-(U4A-PA5-Pad15)") (class "Default")
      (node (ref "U4") (pin "15") (pinfunction "PA5_15") (pintype "bidirectional"))
    )
    (net (code "68") (name "unconnected-(U4A-PA8-Pad29)") (class "Default")
      (node (ref "U4") (pin "29") (pinfunction "PA8_29") (pintype "bidirectional"))
    )
    (net (code "69") (name "unconnected-(U4A-PA11-Pad32)") (class "Default")
      (node (ref "U4") (pin "32") (pinfunction "PA11_32") (pintype "bidirectional"))
    )
    (net (code "70") (name "unconnected-(U4A-PA12-Pad33)") (class "Default")
      (node (ref "U4") (pin "33") (pinfunction "PA12_33") (pintype "bidirectional"))
    )
    (net (code "71") (name "unconnected-(U4A-PA15-Pad38)") (class "Default")
      (node (ref "U4") (pin "38") (pinfunction "PA15_38") (pintype "bidirectional"))
    )
    (net (code "72") (name "unconnected-(U4A-PB0-Pad18)") (class "Default")
      (node (ref "U4") (pin "18") (pinfunction "PB0_18") (pintype "bidirectional"))
    )
    (net (code "73") (name "unconnected-(U4A-PB1-Pad19)") (class "Default")
      (node (ref "U4") (pin "19") (pinfunction "PB1_19") (pintype "bidirectional"))
    )
    (net (code "74") (name "unconnected-(U4A-PB6-Pad42)") (class "Default")
      (node (ref "U4") (pin "42") (pinfunction "PB6_42") (pintype "bidirectional"))
    )
    (net (code "75") (name "unconnected-(U4A-PB7-Pad43)") (class "Default")
      (node (ref "U4") (pin "43") (pinfunction "PB7_43") (pintype "bidirectional"))
    )
    (net (code "76") (name "unconnected-(U4A-PB8-Pad45)") (class "Default")
      (node (ref "U4") (pin "45") (pinfunction "PB8_45") (pintype "bidirectional"))
    )
    (net (code "77") (name "unconnected-(U4A-PB9-Pad46)") (class "Default")
      (node (ref "U4") (pin "46") (pinfunction "PB9_46") (pintype "bidirectional"))
    )
    (net (code "78") (name "unconnected-(U4A-PC13-Pad2)") (class "Default")
      (node (ref "U4") (pin "2") (pinfunction "PC13_2") (pintype "bidirectional"))
    )
    (net (code "79") (name "unconnected-(U4A-PC14-Pad3)") (class "Default")
      (node (ref "U4") (pin "3") (pinfunction "PC14_3") (pintype "bidirectional"))
    )
    (net (code "80") (name "unconnected-(U4A-PC15-Pad4)") (class "Default")
      (node (ref "U4") (pin "4") (pinfunction "PC15_4") (pintype "bidirectional"))
    )
  )
)
